# SPI_Extender.net
KiCad netlist of a schematic drawn in Altium Designer
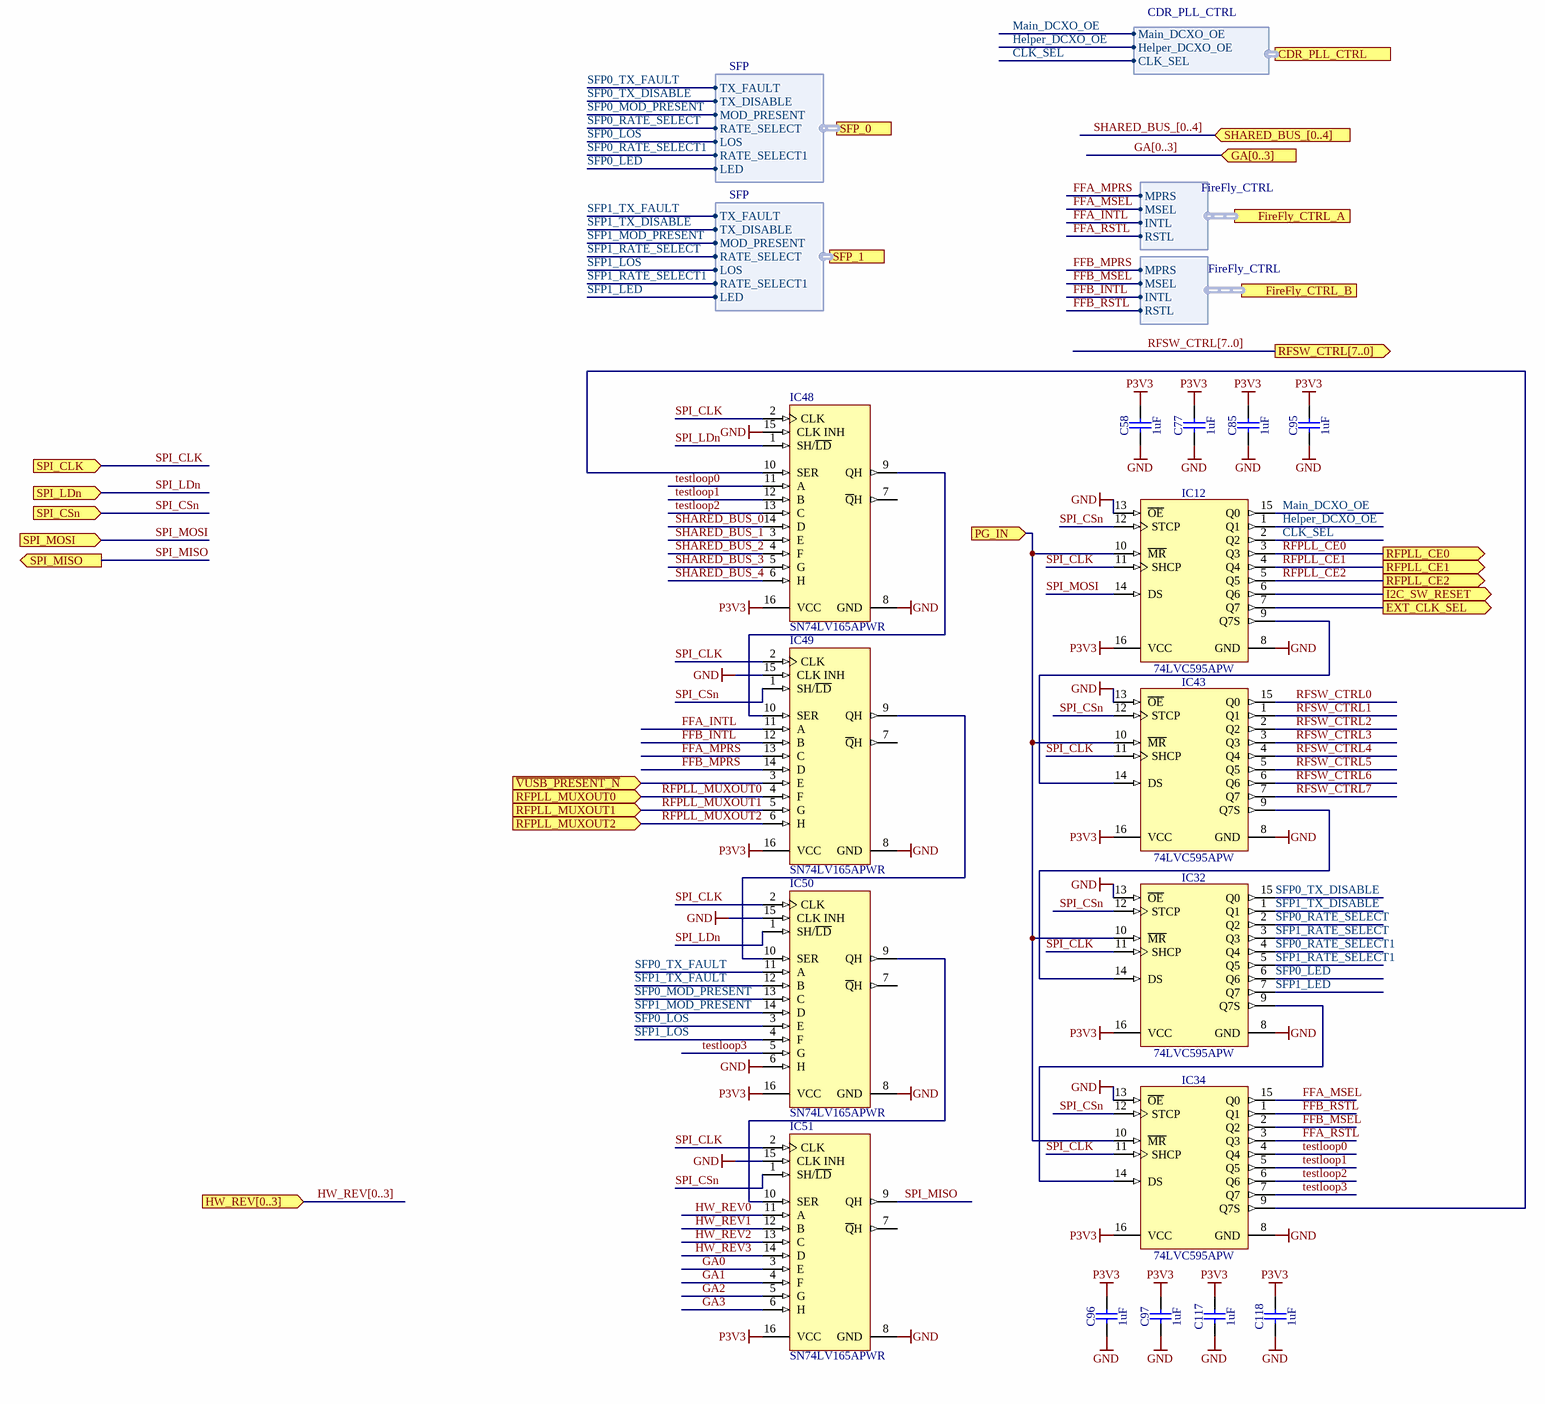
[diagram p0: SPI_Extender.SchDoc]

(export (version "E")
  (design (tool "Eeschema 10.0.6"))
  (components
    (comp (ref "C58")
      (value "1uF")
      (footprint "CAPC1608X87N")
      (description "Non-polarised capacitor")
      (fields
        (field (name "PART NUMBER") "CC0603_1UF_25V_10%_X7R")
        (field (name "VOLTAGE") "25V")
        (field (name "AUTHOR") "CERN DEM JLC")
      )
      (libsource (lib "Capacitors") (part "Capacitor - non polarized"))
    )
    (comp (ref "C77")
      (value "1uF")
      (footprint "CAPC1608X87N")
      (description "Non-polarised capacitor")
      (fields
        (field (name "PART NUMBER") "CC0603_1UF_25V_10%_X7R")
        (field (name "VOLTAGE") "25V")
        (field (name "AUTHOR") "CERN DEM JLC")
      )
      (libsource (lib "Capacitors") (part "Capacitor - non polarized"))
    )
    (comp (ref "C85")
      (value "1uF")
      (footprint "CAPC1608X87N")
      (description "Non-polarised capacitor")
      (fields
        (field (name "PART NUMBER") "CC0603_1UF_25V_10%_X7R")
        (field (name "VOLTAGE") "25V")
        (field (name "AUTHOR") "CERN DEM JLC")
      )
      (libsource (lib "Capacitors") (part "Capacitor - non polarized"))
    )
    (comp (ref "C95")
      (value "1uF")
      (footprint "CAPC1608X87N")
      (description "Non-polarised capacitor")
      (fields
        (field (name "PART NUMBER") "CC0603_1UF_25V_10%_X7R")
        (field (name "VOLTAGE") "25V")
        (field (name "AUTHOR") "CERN DEM JLC")
      )
      (libsource (lib "Capacitors") (part "Capacitor - non polarized"))
    )
    (comp (ref "C96")
      (value "1uF")
      (footprint "CAPC1608X87N")
      (description "Non-polarised capacitor")
      (fields
        (field (name "PART NUMBER") "CC0603_1UF_25V_10%_X7R")
        (field (name "VOLTAGE") "25V")
        (field (name "AUTHOR") "CERN DEM JLC")
      )
      (libsource (lib "Capacitors") (part "Capacitor - non polarized"))
    )
    (comp (ref "C97")
      (value "1uF")
      (footprint "CAPC1608X87N")
      (description "Non-polarised capacitor")
      (fields
        (field (name "PART NUMBER") "CC0603_1UF_25V_10%_X7R")
        (field (name "VOLTAGE") "25V")
        (field (name "AUTHOR") "CERN DEM JLC")
      )
      (libsource (lib "Capacitors") (part "Capacitor - non polarized"))
    )
    (comp (ref "C117")
      (value "1uF")
      (footprint "CAPC1608X87N")
      (description "Non-polarised capacitor")
      (fields
        (field (name "PART NUMBER") "CC0603_1UF_25V_10%_X7R")
        (field (name "VOLTAGE") "25V")
        (field (name "AUTHOR") "CERN DEM JLC")
      )
      (libsource (lib "Capacitors") (part "Capacitor - non polarized"))
    )
    (comp (ref "C118")
      (value "1uF")
      (footprint "CAPC1608X87N")
      (description "Non-polarised capacitor")
      (fields
        (field (name "PART NUMBER") "CC0603_1UF_25V_10%_X7R")
        (field (name "VOLTAGE") "25V")
        (field (name "AUTHOR") "CERN DEM JLC")
      )
      (libsource (lib "Capacitors") (part "Capacitor - non polarized"))
    )
    (comp (ref "IC12")
      (value "74LVC595APW")
      (footprint "SOP65P640X110-16N")
      (description "8-Bit Shift Register With 3-State Output Register")
      (fields (field (name "MANUFACTURER") "NEXPERIA") (field (name "AUTHOR") "CERN DEM HF"))
      (libsource (lib "ICs And Semiconductors") (part "74LVC595"))
    )
    (comp (ref "IC32")
      (value "74LVC595APW")
      (footprint "SOP65P640X110-16N")
      (description "8-Bit Shift Register With 3-State Output Register")
      (fields (field (name "MANUFACTURER") "NEXPERIA") (field (name "AUTHOR") "CERN DEM HF"))
      (libsource (lib "ICs And Semiconductors") (part "74LVC595"))
    )
    (comp (ref "IC34")
      (value "74LVC595APW")
      (footprint "SOP65P640X110-16N")
      (description "8-Bit Shift Register With 3-State Output Register")
      (fields (field (name "MANUFACTURER") "NEXPERIA") (field (name "AUTHOR") "CERN DEM HF"))
      (libsource (lib "ICs And Semiconductors") (part "74LVC595"))
    )
    (comp (ref "IC43")
      (value "74LVC595APW")
      (footprint "SOP65P640X110-16N")
      (description "8-Bit Shift Register With 3-State Output Register")
      (fields (field (name "MANUFACTURER") "NEXPERIA") (field (name "AUTHOR") "CERN DEM HF"))
      (libsource (lib "ICs And Semiconductors") (part "74LVC595"))
    )
    (comp (ref "IC48")
      (value "SN74LV165APWR")
      (footprint "PW0016A_M")
      (description "Parallel-Load 8-Bit Shift Registers, PW0016A, LARGE T&R")
      (fields
        (field (name "GENERIC PART NUMBER") "SN74LV165A")
        (field (name "MANUFACTURER") "Texas Instruments")
      )
      (libsource (lib "Altium Content Vault") (part "TI-SNX4XXX165X-16"))
    )
    (comp (ref "IC49")
      (value "SN74LV165APWR")
      (footprint "PW0016A_M")
      (description "Parallel-Load 8-Bit Shift Registers, PW0016A, LARGE T&R")
      (fields
        (field (name "GENERIC PART NUMBER") "SN74LV165A")
        (field (name "MANUFACTURER") "Texas Instruments")
      )
      (libsource (lib "Altium Content Vault") (part "TI-SNX4XXX165X-16"))
    )
    (comp (ref "IC50")
      (value "SN74LV165APWR")
      (footprint "PW0016A_M")
      (description "Parallel-Load 8-Bit Shift Registers, PW0016A, LARGE T&R")
      (fields
        (field (name "GENERIC PART NUMBER") "SN74LV165A")
        (field (name "MANUFACTURER") "Texas Instruments")
      )
      (libsource (lib "Altium Content Vault") (part "TI-SNX4XXX165X-16"))
    )
    (comp (ref "IC51")
      (value "SN74LV165APWR")
      (footprint "PW0016A_M")
      (description "Parallel-Load 8-Bit Shift Registers, PW0016A, LARGE T&R")
      (fields
        (field (name "GENERIC PART NUMBER") "SN74LV165A")
        (field (name "MANUFACTURER") "Texas Instruments")
      )
      (libsource (lib "Altium Content Vault") (part "TI-SNX4XXX165X-16"))
    )
  )
  (nets
    (net (code "4") (name "/CLK_SEL") (class "Default")
      (node (ref "IC12") (pin "2") (pinfunction "Q2_2") (pintype "output"))
    )
    (net (code "5") (name "/EXT_CLK_SEL") (class "Default")
      (node (ref "IC12") (pin "7") (pinfunction "Q7_7") (pintype "output"))
    )
    (net (code "6") (name "/FFA_INTL") (class "Default")
      (node (ref "IC49") (pin "11") (pinfunction "A_11") (pintype "input"))
    )
    (net (code "7") (name "/FFA_MPRS") (class "Default")
      (node (ref "IC49") (pin "13") (pinfunction "C_13") (pintype "input"))
    )
    (net (code "8") (name "/FFA_MSEL") (class "Default")
      (node (ref "IC34") (pin "15") (pinfunction "Q0_15") (pintype "output"))
    )
    (net (code "9") (name "/FFA_RSTL") (class "Default")
      (node (ref "IC34") (pin "3") (pinfunction "Q3_3") (pintype "output"))
    )
    (net (code "10") (name "/FFB_INTL") (class "Default")
      (node (ref "IC49") (pin "12") (pinfunction "B_12") (pintype "input"))
    )
    (net (code "11") (name "/FFB_MPRS") (class "Default")
      (node (ref "IC49") (pin "14") (pinfunction "D_14") (pintype "input"))
    )
    (net (code "12") (name "/FFB_MSEL") (class "Default")
      (node (ref "IC34") (pin "2") (pinfunction "Q2_2") (pintype "output"))
    )
    (net (code "13") (name "/FFB_RSTL") (class "Default")
      (node (ref "IC34") (pin "1") (pinfunction "Q1_1") (pintype "output"))
    )
    (net (code "14") (name "/GA0") (class "Default")
      (node (ref "IC51") (pin "3") (pinfunction "E_3") (pintype "input"))
    )
    (net (code "15") (name "/GA1") (class "Default")
      (node (ref "IC51") (pin "4") (pinfunction "F_4") (pintype "input"))
    )
    (net (code "16") (name "/GA2") (class "Default")
      (node (ref "IC51") (pin "5") (pinfunction "G_5") (pintype "input"))
    )
    (net (code "17") (name "/GA3") (class "Default")
      (node (ref "IC51") (pin "6") (pinfunction "H_6") (pintype "input"))
    )
    (net (code "19") (name "/HW_REV0") (class "Default")
      (node (ref "IC51") (pin "11") (pinfunction "A_11") (pintype "input"))
    )
    (net (code "20") (name "/HW_REV1") (class "Default")
      (node (ref "IC51") (pin "12") (pinfunction "B_12") (pintype "input"))
    )
    (net (code "21") (name "/HW_REV2") (class "Default")
      (node (ref "IC51") (pin "13") (pinfunction "C_13") (pintype "input"))
    )
    (net (code "22") (name "/HW_REV3") (class "Default")
      (node (ref "IC51") (pin "14") (pinfunction "D_14") (pintype "input"))
    )
    (net (code "24") (name "/Helper_DCXO_OE") (class "Default")
      (node (ref "IC12") (pin "1") (pinfunction "Q1_1") (pintype "output"))
    )
    (net (code "25") (name "/I2C_SW_RESET") (class "Default")
      (node (ref "IC12") (pin "6") (pinfunction "Q6_6") (pintype "output"))
    )
    (net (code "26") (name "/Main_DCXO_OE") (class "Default")
      (node (ref "IC12") (pin "15") (pinfunction "Q0_15") (pintype "output"))
    )
    (net (code "27") (name "/PG_IN") (class "Default")
      (node (ref "IC12") (pin "10") (pinfunction "~{MR}_10") (pintype "input"))
      (node (ref "IC32") (pin "10") (pinfunction "~{MR}_10") (pintype "input"))
      (node (ref "IC34") (pin "10") (pinfunction "~{MR}_10") (pintype "input"))
      (node (ref "IC43") (pin "10") (pinfunction "~{MR}_10") (pintype "input"))
    )
    (net (code "28") (name "/RFPLL_CE0") (class "Default")
      (node (ref "IC12") (pin "3") (pinfunction "Q3_3") (pintype "output"))
    )
    (net (code "29") (name "/RFPLL_CE1") (class "Default")
      (node (ref "IC12") (pin "4") (pinfunction "Q4_4") (pintype "output"))
    )
    (net (code "30") (name "/RFPLL_CE2") (class "Default")
      (node (ref "IC12") (pin "5") (pinfunction "Q5_5") (pintype "output"))
    )
    (net (code "31") (name "/RFPLL_MUXOUT0") (class "Default")
      (node (ref "IC49") (pin "4") (pinfunction "F_4") (pintype "input"))
    )
    (net (code "32") (name "/RFPLL_MUXOUT1") (class "Default")
      (node (ref "IC49") (pin "5") (pinfunction "G_5") (pintype "input"))
    )
    (net (code "33") (name "/RFPLL_MUXOUT2") (class "Default")
      (node (ref "IC49") (pin "6") (pinfunction "H_6") (pintype "input"))
    )
    (net (code "34") (name "/RFSW_CTRL0") (class "Default")
      (node (ref "IC43") (pin "15") (pinfunction "Q0_15") (pintype "output"))
    )
    (net (code "35") (name "/RFSW_CTRL1") (class "Default")
      (node (ref "IC43") (pin "1") (pinfunction "Q1_1") (pintype "output"))
    )
    (net (code "36") (name "/RFSW_CTRL2") (class "Default")
      (node (ref "IC43") (pin "2") (pinfunction "Q2_2") (pintype "output"))
    )
    (net (code "37") (name "/RFSW_CTRL3") (class "Default")
      (node (ref "IC43") (pin "3") (pinfunction "Q3_3") (pintype "output"))
    )
    (net (code "38") (name "/RFSW_CTRL4") (class "Default")
      (node (ref "IC43") (pin "4") (pinfunction "Q4_4") (pintype "output"))
    )
    (net (code "39") (name "/RFSW_CTRL5") (class "Default")
      (node (ref "IC43") (pin "5") (pinfunction "Q5_5") (pintype "output"))
    )
    (net (code "40") (name "/RFSW_CTRL6") (class "Default")
      (node (ref "IC43") (pin "6") (pinfunction "Q6_6") (pintype "output"))
    )
    (net (code "41") (name "/RFSW_CTRL7") (class "Default")
      (node (ref "IC43") (pin "7") (pinfunction "Q7_7") (pintype "output"))
    )
    (net (code "43") (name "/SFP0_LED") (class "Default")
      (node (ref "IC32") (pin "6") (pinfunction "Q6_6") (pintype "output"))
    )
    (net (code "44") (name "/SFP0_LOS") (class "Default")
      (node (ref "IC50") (pin "3") (pinfunction "E_3") (pintype "input"))
    )
    (net (code "45") (name "/SFP0_MOD_PRESENT") (class "Default")
      (node (ref "IC50") (pin "13") (pinfunction "C_13") (pintype "input"))
    )
    (net (code "46") (name "/SFP0_RATE_SELECT") (class "Default")
      (node (ref "IC32") (pin "2") (pinfunction "Q2_2") (pintype "output"))
    )
    (net (code "47") (name "/SFP0_RATE_SELECT1") (class "Default")
      (node (ref "IC32") (pin "4") (pinfunction "Q4_4") (pintype "output"))
    )
    (net (code "48") (name "/SFP0_TX_DISABLE") (class "Default")
      (node (ref "IC32") (pin "15") (pinfunction "Q0_15") (pintype "output"))
    )
    (net (code "49") (name "/SFP0_TX_FAULT") (class "Default")
      (node (ref "IC50") (pin "11") (pinfunction "A_11") (pintype "input"))
    )
    (net (code "50") (name "/SFP1_LED") (class "Default")
      (node (ref "IC32") (pin "7") (pinfunction "Q7_7") (pintype "output"))
    )
    (net (code "51") (name "/SFP1_LOS") (class "Default")
      (node (ref "IC50") (pin "4") (pinfunction "F_4") (pintype "input"))
    )
    (net (code "52") (name "/SFP1_MOD_PRESENT") (class "Default")
      (node (ref "IC50") (pin "14") (pinfunction "D_14") (pintype "input"))
    )
    (net (code "53") (name "/SFP1_RATE_SELECT") (class "Default")
      (node (ref "IC32") (pin "3") (pinfunction "Q3_3") (pintype "output"))
    )
    (net (code "54") (name "/SFP1_RATE_SELECT1") (class "Default")
      (node (ref "IC32") (pin "5") (pinfunction "Q5_5") (pintype "output"))
    )
    (net (code "55") (name "/SFP1_TX_DISABLE") (class "Default")
      (node (ref "IC32") (pin "1") (pinfunction "Q1_1") (pintype "output"))
    )
    (net (code "56") (name "/SFP1_TX_FAULT") (class "Default")
      (node (ref "IC50") (pin "12") (pinfunction "B_12") (pintype "input"))
    )
    (net (code "57") (name "/SHARED_BUS_0") (class "Default")
      (node (ref "IC48") (pin "14") (pinfunction "D_14") (pintype "input"))
    )
    (net (code "58") (name "/SHARED_BUS_1") (class "Default")
      (node (ref "IC48") (pin "3") (pinfunction "E_3") (pintype "input"))
    )
    (net (code "59") (name "/SHARED_BUS_2") (class "Default")
      (node (ref "IC48") (pin "4") (pinfunction "F_4") (pintype "input"))
    )
    (net (code "60") (name "/SHARED_BUS_3") (class "Default")
      (node (ref "IC48") (pin "5") (pinfunction "G_5") (pintype "input"))
    )
    (net (code "61") (name "/SHARED_BUS_4") (class "Default")
      (node (ref "IC48") (pin "6") (pinfunction "H_6") (pintype "input"))
    )
    (net (code "63") (name "/SPI_CLK") (class "Default")
      (node (ref "IC12") (pin "11") (pinfunction "SHCP_11") (pintype "input"))
      (node (ref "IC32") (pin "11") (pinfunction "SHCP_11") (pintype "input"))
      (node (ref "IC34") (pin "11") (pinfunction "SHCP_11") (pintype "input"))
      (node (ref "IC43") (pin "11") (pinfunction "SHCP_11") (pintype "input"))
      (node (ref "IC48") (pin "2") (pinfunction "CLK_2") (pintype "input"))
      (node (ref "IC49") (pin "2") (pinfunction "CLK_2") (pintype "input"))
      (node (ref "IC50") (pin "2") (pinfunction "CLK_2") (pintype "input"))
      (node (ref "IC51") (pin "2") (pinfunction "CLK_2") (pintype "input"))
    )
    (net (code "64") (name "/SPI_CSn") (class "Default")
      (node (ref "IC12") (pin "12") (pinfunction "STCP_12") (pintype "input"))
      (node (ref "IC32") (pin "12") (pinfunction "STCP_12") (pintype "input"))
      (node (ref "IC34") (pin "12") (pinfunction "STCP_12") (pintype "input"))
      (node (ref "IC43") (pin "12") (pinfunction "STCP_12") (pintype "input"))
      (node (ref "IC49") (pin "1") (pinfunction "SH/~{LD}_1") (pintype "input"))
      (node (ref "IC51") (pin "1") (pinfunction "SH/~{LD}_1") (pintype "input"))
    )
    (net (code "65") (name "/SPI_LDn") (class "Default")
      (node (ref "IC48") (pin "1") (pinfunction "SH/~{LD}_1") (pintype "input"))
      (node (ref "IC50") (pin "1") (pinfunction "SH/~{LD}_1") (pintype "input"))
    )
    (net (code "66") (name "/SPI_MISO") (class "Default")
      (node (ref "IC51") (pin "9") (pinfunction "QH_9") (pintype "output"))
    )
    (net (code "67") (name "/SPI_MOSI") (class "Default")
      (node (ref "IC12") (pin "14") (pinfunction "DS_14") (pintype "input"))
    )
    (net (code "68") (name "/VUSB_PRESENT_N") (class "Default")
      (node (ref "IC49") (pin "3") (pinfunction "E_3") (pintype "input"))
    )
    (net (code "69") (name "/testloop0") (class "Default")
      (node (ref "IC34") (pin "4") (pinfunction "Q4_4") (pintype "output"))
      (node (ref "IC48") (pin "11") (pinfunction "A_11") (pintype "input"))
    )
    (net (code "70") (name "/testloop1") (class "Default")
      (node (ref "IC34") (pin "5") (pinfunction "Q5_5") (pintype "output"))
      (node (ref "IC48") (pin "12") (pinfunction "B_12") (pintype "input"))
    )
    (net (code "71") (name "/testloop2") (class "Default")
      (node (ref "IC34") (pin "6") (pinfunction "Q6_6") (pintype "output"))
      (node (ref "IC48") (pin "13") (pinfunction "C_13") (pintype "input"))
    )
    (net (code "72") (name "/testloop3") (class "Default")
      (node (ref "IC34") (pin "7") (pinfunction "Q7_7") (pintype "output"))
      (node (ref "IC50") (pin "5") (pinfunction "G_5") (pintype "input"))
    )
    (net (code "76") (name "GND") (class "Default")
      (node (ref "C117") (pin "1") (pinfunction "1_1") (pintype "passive"))
      (node (ref "C118") (pin "1") (pinfunction "1_1") (pintype "passive"))
      (node (ref "C58") (pin "1") (pinfunction "1_1") (pintype "passive"))
      (node (ref "C77") (pin "1") (pinfunction "1_1") (pintype "passive"))
      (node (ref "C85") (pin "1") (pinfunction "1_1") (pintype "passive"))
      (node (ref "C95") (pin "1") (pinfunction "1_1") (pintype "passive"))
      (node (ref "C96") (pin "1") (pinfunction "1_1") (pintype "passive"))
      (node (ref "C97") (pin "1") (pinfunction "1_1") (pintype "passive"))
      (node (ref "IC12") (pin "13") (pinfunction "~{OE}_13") (pintype "input"))
      (node (ref "IC12") (pin "8") (pinfunction "GND_8") (pintype "power_in"))
      (node (ref "IC32") (pin "13") (pinfunction "~{OE}_13") (pintype "input"))
      (node (ref "IC32") (pin "8") (pinfunction "GND_8") (pintype "power_in"))
      (node (ref "IC34") (pin "13") (pinfunction "~{OE}_13") (pintype "input"))
      (node (ref "IC34") (pin "8") (pinfunction "GND_8") (pintype "power_in"))
      (node (ref "IC43") (pin "13") (pinfunction "~{OE}_13") (pintype "input"))
      (node (ref "IC43") (pin "8") (pinfunction "GND_8") (pintype "power_in"))
      (node (ref "IC48") (pin "15") (pinfunction "CLK_INH_15") (pintype "input"))
      (node (ref "IC48") (pin "8") (pinfunction "GND_8") (pintype "power_in"))
      (node (ref "IC49") (pin "15") (pinfunction "CLK_INH_15") (pintype "input"))
      (node (ref "IC49") (pin "8") (pinfunction "GND_8") (pintype "power_in"))
      (node (ref "IC50") (pin "15") (pinfunction "CLK_INH_15") (pintype "input"))
      (node (ref "IC50") (pin "6") (pinfunction "H_6") (pintype "input"))
      (node (ref "IC50") (pin "8") (pinfunction "GND_8") (pintype "power_in"))
      (node (ref "IC51") (pin "15") (pinfunction "CLK_INH_15") (pintype "input"))
      (node (ref "IC51") (pin "8") (pinfunction "GND_8") (pintype "power_in"))
    )
    (net (code "77") (name "Net-(IC12-Q7S)") (class "Default")
      (node (ref "IC12") (pin "9") (pinfunction "Q7S_9") (pintype "output"))
      (node (ref "IC43") (pin "14") (pinfunction "DS_14") (pintype "input"))
    )
    (net (code "78") (name "Net-(IC32-DS)") (class "Default")
      (node (ref "IC32") (pin "14") (pinfunction "DS_14") (pintype "input"))
      (node (ref "IC43") (pin "9") (pinfunction "Q7S_9") (pintype "output"))
    )
    (net (code "79") (name "Net-(IC32-Q7S)") (class "Default")
      (node (ref "IC32") (pin "9") (pinfunction "Q7S_9") (pintype "output"))
      (node (ref "IC34") (pin "14") (pinfunction "DS_14") (pintype "input"))
    )
    (net (code "80") (name "Net-(IC34-Q7S)") (class "Default")
      (node (ref "IC34") (pin "9") (pinfunction "Q7S_9") (pintype "output"))
      (node (ref "IC48") (pin "10") (pinfunction "SER_10") (pintype "input"))
    )
    (net (code "81") (name "Net-(IC48-QH)") (class "Default")
      (node (ref "IC48") (pin "9") (pinfunction "QH_9") (pintype "output"))
      (node (ref "IC49") (pin "10") (pinfunction "SER_10") (pintype "input"))
    )
    (net (code "82") (name "Net-(IC49-QH)") (class "Default")
      (node (ref "IC49") (pin "9") (pinfunction "QH_9") (pintype "output"))
      (node (ref "IC50") (pin "10") (pinfunction "SER_10") (pintype "input"))
    )
    (net (code "83") (name "Net-(IC50-QH)") (class "Default")
      (node (ref "IC50") (pin "9") (pinfunction "QH_9") (pintype "output"))
      (node (ref "IC51") (pin "10") (pinfunction "SER_10") (pintype "input"))
    )
    (net (code "84") (name "P3V3") (class "Default")
      (node (ref "C117") (pin "2") (pinfunction "2_2") (pintype "passive"))
      (node (ref "C118") (pin "2") (pinfunction "2_2") (pintype "passive"))
      (node (ref "C58") (pin "2") (pinfunction "2_2") (pintype "passive"))
      (node (ref "C77") (pin "2") (pinfunction "2_2") (pintype "passive"))
      (node (ref "C85") (pin "2") (pinfunction "2_2") (pintype "passive"))
      (node (ref "C95") (pin "2") (pinfunction "2_2") (pintype "passive"))
      (node (ref "C96") (pin "2") (pinfunction "2_2") (pintype "passive"))
      (node (ref "C97") (pin "2") (pinfunction "2_2") (pintype "passive"))
      (node (ref "IC12") (pin "16") (pinfunction "VCC_16") (pintype "power_in"))
      (node (ref "IC32") (pin "16") (pinfunction "VCC_16") (pintype "power_in"))
      (node (ref "IC34") (pin "16") (pinfunction "VCC_16") (pintype "power_in"))
      (node (ref "IC43") (pin "16") (pinfunction "VCC_16") (pintype "power_in"))
      (node (ref "IC48") (pin "16") (pinfunction "VCC_16") (pintype "power_in"))
      (node (ref "IC49") (pin "16") (pinfunction "VCC_16") (pintype "power_in"))
      (node (ref "IC50") (pin "16") (pinfunction "VCC_16") (pintype "power_in"))
      (node (ref "IC51") (pin "16") (pinfunction "VCC_16") (pintype "power_in"))
    )
    (net (code "85") (name "unconnected-(IC48-~{Q}H-Pad7)") (class "Default")
      (node (ref "IC48") (pin "7") (pinfunction "~{Q}H_7") (pintype "output"))
    )
    (net (code "86") (name "unconnected-(IC49-~{Q}H-Pad7)") (class "Default")
      (node (ref "IC49") (pin "7") (pinfunction "~{Q}H_7") (pintype "output"))
    )
    (net (code "87") (name "unconnected-(IC50-~{Q}H-Pad7)") (class "Default")
      (node (ref "IC50") (pin "7") (pinfunction "~{Q}H_7") (pintype "output"))
    )
    (net (code "88") (name "unconnected-(IC51-~{Q}H-Pad7)") (class "Default")
      (node (ref "IC51") (pin "7") (pinfunction "~{Q}H_7") (pintype "output"))
    )
  )
)
